# ProProject_Access_Control_Interface_2024.net
KiCad netlist of a schematic drawn in EasyEDA Pro
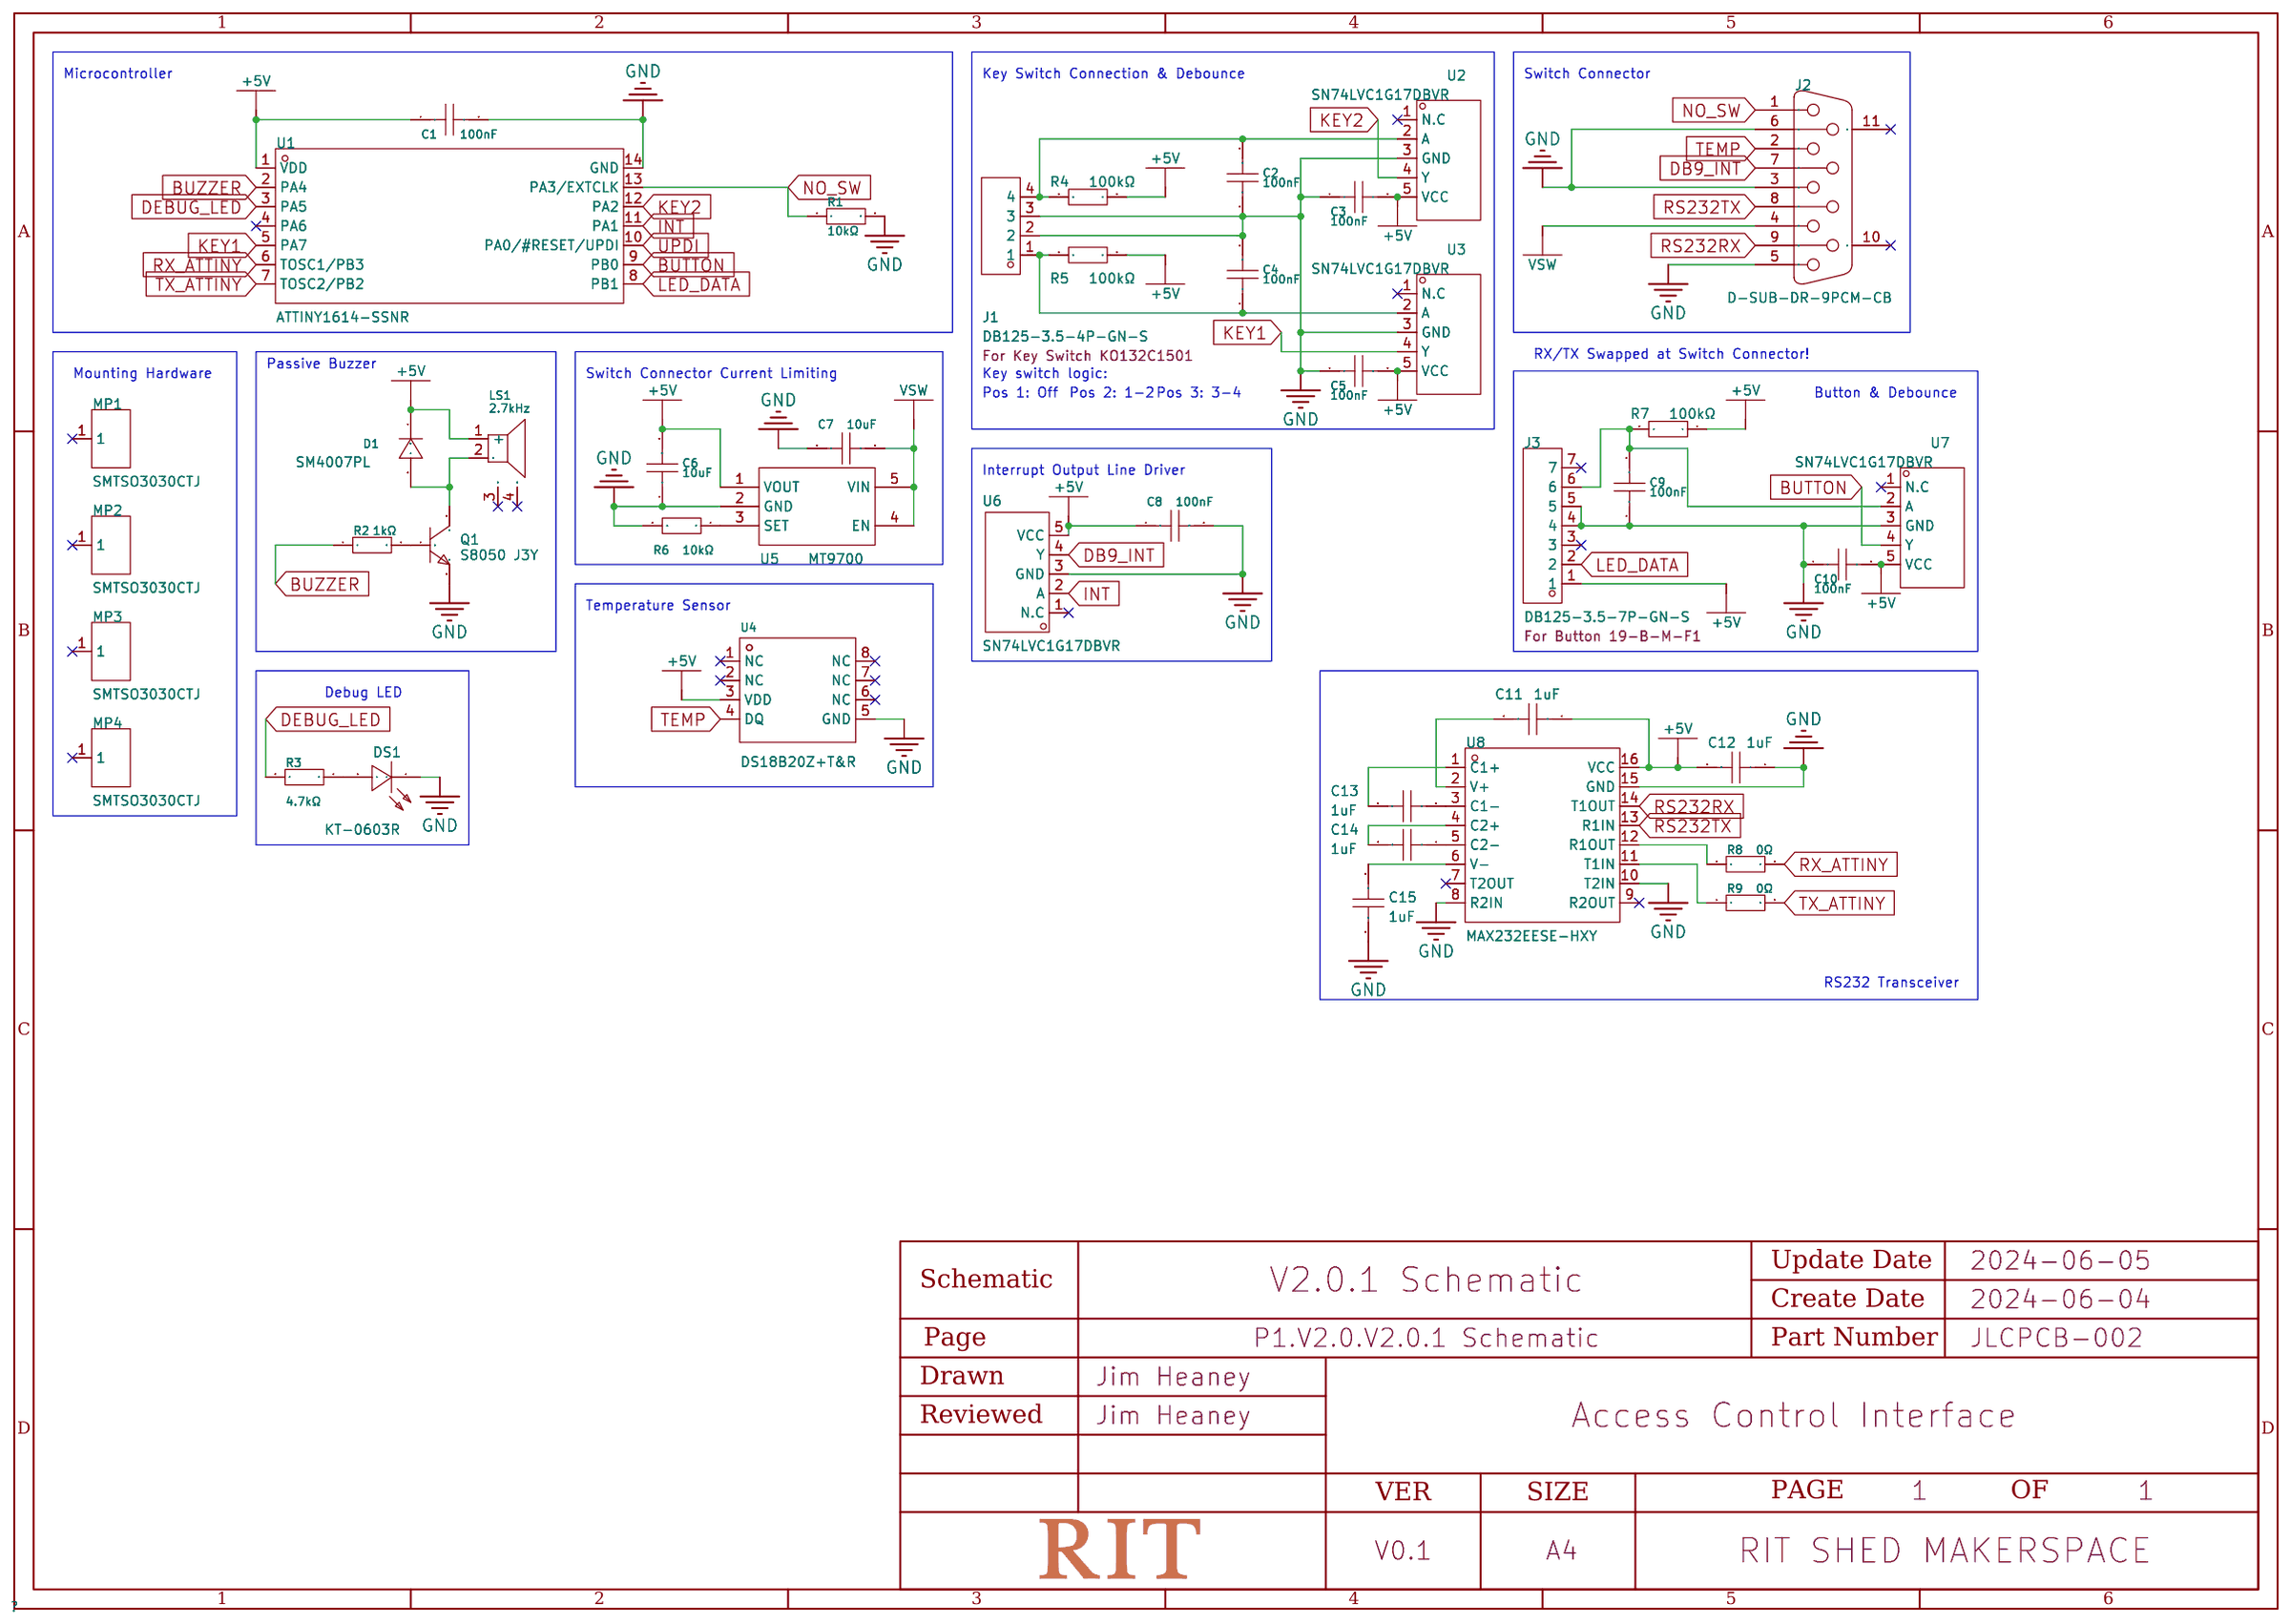
[diagram p0: schematic sheet]

(export (version "E")
  (design (tool "Eeschema 10.0.6"))
  (components
    (comp (ref "C1")
      (value "100nF")
      (footprint "easyedapro:C0603")
      (fields
        (field (name "Manufacturer Part") "CC0603KRX7R9BB104")
        (field (name "Manufacturer") "YAGEO(国巨)")
      )
      (libsource (lib "easyedapro") (part "CC0603KRX7R9BB104"))
    )
    (comp (ref "C2")
      (value "100nF")
      (footprint "easyedapro:C0603")
      (fields
        (field (name "Manufacturer Part") "CC0603KRX7R9BB104")
        (field (name "Manufacturer") "YAGEO(国巨)")
      )
      (libsource (lib "easyedapro") (part "CC0603KRX7R9BB104"))
    )
    (comp (ref "C3")
      (value "100nF")
      (footprint "easyedapro:C0603")
      (fields
        (field (name "Manufacturer Part") "CC0603KRX7R9BB104")
        (field (name "Manufacturer") "YAGEO(国巨)")
      )
      (libsource (lib "easyedapro") (part "CC0603KRX7R9BB104"))
    )
    (comp (ref "C4")
      (value "100nF")
      (footprint "easyedapro:C0603")
      (fields
        (field (name "Manufacturer Part") "CC0603KRX7R9BB104")
        (field (name "Manufacturer") "YAGEO(国巨)")
      )
      (libsource (lib "easyedapro") (part "CC0603KRX7R9BB104"))
    )
    (comp (ref "C5")
      (value "100nF")
      (footprint "easyedapro:C0603")
      (fields
        (field (name "Manufacturer Part") "CC0603KRX7R9BB104")
        (field (name "Manufacturer") "YAGEO(国巨)")
      )
      (libsource (lib "easyedapro") (part "CC0603KRX7R9BB104"))
    )
    (comp (ref "C6")
      (value "10uF")
      (footprint "easyedapro:C0603")
      (fields
        (field (name "Manufacturer Part") "CL10A106MA8NRNC")
        (field (name "Manufacturer") "SAMSUNG(三星)")
      )
      (libsource (lib "easyedapro") (part "CL10A106MA8NRNC"))
    )
    (comp (ref "C7")
      (value "10uF")
      (footprint "easyedapro:C0603")
      (fields
        (field (name "Manufacturer Part") "CL10A106MA8NRNC")
        (field (name "Manufacturer") "SAMSUNG(三星)")
      )
      (libsource (lib "easyedapro") (part "CL10A106MA8NRNC"))
    )
    (comp (ref "C8")
      (value "100nF")
      (footprint "easyedapro:C0603")
      (fields
        (field (name "Manufacturer Part") "CC0603KRX7R9BB104")
        (field (name "Manufacturer") "YAGEO(国巨)")
      )
      (libsource (lib "easyedapro") (part "CC0603KRX7R9BB104"))
    )
    (comp (ref "C9")
      (value "100nF")
      (footprint "easyedapro:C0603")
      (fields
        (field (name "Manufacturer Part") "CC0603KRX7R9BB104")
        (field (name "Manufacturer") "YAGEO(国巨)")
      )
      (libsource (lib "easyedapro") (part "CC0603KRX7R9BB104"))
    )
    (comp (ref "C10")
      (value "100nF")
      (footprint "easyedapro:C0603")
      (fields
        (field (name "Manufacturer Part") "CC0603KRX7R9BB104")
        (field (name "Manufacturer") "YAGEO(国巨)")
      )
      (libsource (lib "easyedapro") (part "CC0603KRX7R9BB104"))
    )
    (comp (ref "C11")
      (value "1uF")
      (footprint "easyedapro:C0603")
      (fields
        (field (name "Manufacturer Part") "CL10A105KB8NNNC")
        (field (name "Manufacturer") "SAMSUNG(三星)")
      )
      (libsource (lib "easyedapro") (part "CL10A105KB8NNNC"))
    )
    (comp (ref "C12")
      (value "1uF")
      (footprint "easyedapro:C0603")
      (fields
        (field (name "Manufacturer Part") "CL10A105KB8NNNC")
        (field (name "Manufacturer") "SAMSUNG(三星)")
      )
      (libsource (lib "easyedapro") (part "CL10A105KB8NNNC"))
    )
    (comp (ref "C13")
      (value "1uF")
      (footprint "easyedapro:C0603")
      (fields
        (field (name "Manufacturer Part") "CL10A105KB8NNNC")
        (field (name "Manufacturer") "SAMSUNG(三星)")
      )
      (libsource (lib "easyedapro") (part "CL10A105KB8NNNC"))
    )
    (comp (ref "C14")
      (value "1uF")
      (footprint "easyedapro:C0603")
      (fields
        (field (name "Manufacturer Part") "CL10A105KB8NNNC")
        (field (name "Manufacturer") "SAMSUNG(三星)")
      )
      (libsource (lib "easyedapro") (part "CL10A105KB8NNNC"))
    )
    (comp (ref "C15")
      (value "1uF")
      (footprint "easyedapro:C0603")
      (fields
        (field (name "Manufacturer Part") "CL10A105KB8NNNC")
        (field (name "Manufacturer") "SAMSUNG(三星)")
      )
      (libsource (lib "easyedapro") (part "CL10A105KB8NNNC"))
    )
    (comp (ref "D1")
      (value "SM4007PL")
      (footprint "easyedapro:SOD-123F_L2.8-W1.8-LS3.7-RD")
      (fields (field (name "Manufacturer") "MDD"))
      (libsource (lib "easyedapro") (part "SM4007PL"))
    )
    (comp (ref "DS1")
      (value "KT-0603R")
      (footprint "easyedapro:LED0603-RD")
      (fields (field (name "Manufacturer") "KENTO"))
      (libsource (lib "easyedapro") (part "KT-0603R"))
    )
    (comp (ref "J1")
      (value "DB125-3.5-4P-GN-S")
      (footprint "easyedapro:CONN-TH_DB125-3.5-4P-GN")
      (description "For Key Switch KO132C1501")
      (fields (field (name "Manufacturer") "DORABO(地博电气)"))
      (libsource (lib "easyedapro") (part "DB125-3.5-4P-GN"))
    )
    (comp (ref "J2")
      (value "D-SUB-DR-9PCM-CB")
      (footprint "easyedapro:DB9-TH_ID09S33E4GV00LF")
      (fields (field (name "Manufacturer") "XUNPU(讯普)"))
      (libsource (lib "easyedapro") (part "D-SUB-DR-9PCM-CB"))
    )
    (comp (ref "J3")
      (value "DB125-3.5-7P-GN-S")
      (footprint "easyedapro:CONN-TH_7P-P3.50_DORABO_DB125-3.5-7P-GN-S")
      (description "For Button 19-B-M-F1")
      (fields (field (name "Manufacturer") "DORABO(地博电气)"))
      (libsource (lib "easyedapro") (part "DB125-3.5-7P-GN-S"))
    )
    (comp (ref "LS1")
      (value "2.7kHz")
      (footprint "easyedapro:BUZ-SMD_4P-L8.5-W8.5-P8.50-TL")
      (fields (field (name "Manufacturer Part") "MLT-8540") (field (name "Manufacturer") "华能"))
      (libsource (lib "easyedapro") (part "MLT-8540"))
    )
    (comp (ref "MP1")
      (value "SMTSO3030CTJ")
      (footprint "easyedapro:SMD_BD5.6-D4.1")
      (description "specifications:M3X3 surface treatment:镀锡 Product Description:- material quality:-")
      (fields (field (name "Manufacturer") "Sinhoo(雄和远景)"))
      (libsource (lib "easyedapro") (part "SMTSO3030CTJ"))
    )
    (comp (ref "MP2")
      (value "SMTSO3030CTJ")
      (footprint "easyedapro:SMD_BD5.6-D4.1")
      (description "specifications:M3X3 surface treatment:镀锡 Product Description:- material quality:-")
      (fields (field (name "Manufacturer") "Sinhoo(雄和远景)"))
      (libsource (lib "easyedapro") (part "SMTSO3030CTJ"))
    )
    (comp (ref "MP3")
      (value "SMTSO3030CTJ")
      (footprint "easyedapro:SMD_BD5.6-D4.1")
      (description "specifications:M3X3 surface treatment:镀锡 Product Description:- material quality:-")
      (fields (field (name "Manufacturer") "Sinhoo(雄和远景)"))
      (libsource (lib "easyedapro") (part "SMTSO3030CTJ"))
    )
    (comp (ref "MP4")
      (value "SMTSO3030CTJ")
      (footprint "easyedapro:SMD_BD5.6-D4.1")
      (description "specifications:M3X3 surface treatment:镀锡 Product Description:- material quality:-")
      (fields (field (name "Manufacturer") "Sinhoo(雄和远景)"))
      (libsource (lib "easyedapro") (part "SMTSO3030CTJ"))
    )
    (comp (ref "Q1")
      (value "S8050 J3Y")
      (footprint "easyedapro:SOT-23-3_L3.0-W1.7-P0.95-LS2.9-BR")
      (fields (field (name "Manufacturer") "CJ(江苏长电/长晶)"))
      (libsource (lib "easyedapro") (part "S8050_C2146"))
    )
    (comp (ref "R1")
      (value "10kΩ")
      (footprint "easyedapro:R0603")
      (fields
        (field (name "Manufacturer Part") "0603WAF1002T5E")
        (field (name "Manufacturer") "UNI-ROYAL(厚声)")
      )
      (libsource (lib "easyedapro") (part "0603WAF1002T5E"))
    )
    (comp (ref "R2")
      (value "1kΩ")
      (footprint "easyedapro:R0603")
      (fields
        (field (name "Manufacturer Part") "0603WAF1001T5E")
        (field (name "Manufacturer") "UNI-ROYAL(厚声)")
      )
      (libsource (lib "easyedapro") (part "0603WAF1001T5E"))
    )
    (comp (ref "R3")
      (value "4.7kΩ")
      (footprint "easyedapro:R0603")
      (fields
        (field (name "Manufacturer Part") "0603WAF4701T5E")
        (field (name "Manufacturer") "UNI-ROYAL(厚声)")
      )
      (libsource (lib "easyedapro") (part "0603WAF4701T5E"))
    )
    (comp (ref "R4")
      (value "100kΩ")
      (footprint "easyedapro:R0603")
      (fields
        (field (name "Manufacturer Part") "0603WAF1003T5E")
        (field (name "Manufacturer") "UNI-ROYAL(厚声)")
      )
      (libsource (lib "easyedapro") (part "0603WAF1003T5E"))
    )
    (comp (ref "R5")
      (value "100kΩ")
      (footprint "easyedapro:R0603")
      (fields
        (field (name "Manufacturer Part") "0603WAF1003T5E")
        (field (name "Manufacturer") "UNI-ROYAL(厚声)")
      )
      (libsource (lib "easyedapro") (part "0603WAF1003T5E"))
    )
    (comp (ref "R6")
      (value "10kΩ")
      (footprint "easyedapro:R0603")
      (fields
        (field (name "Manufacturer Part") "0603WAF1002T5E")
        (field (name "Manufacturer") "UNI-ROYAL(厚声)")
      )
      (libsource (lib "easyedapro") (part "0603WAF1002T5E"))
    )
    (comp (ref "R7")
      (value "100kΩ")
      (footprint "easyedapro:R0603")
      (fields
        (field (name "Manufacturer Part") "0603WAF1003T5E")
        (field (name "Manufacturer") "UNI-ROYAL(厚声)")
      )
      (libsource (lib "easyedapro") (part "0603WAF1003T5E"))
    )
    (comp (ref "R8")
      (value "0Ω")
      (footprint "easyedapro:R1206")
      (fields
        (field (name "Manufacturer Part") "1206W4F0000T5E")
        (field (name "Manufacturer") "UNI-ROYAL(厚声)")
      )
      (libsource (lib "easyedapro") (part "1206W4F0000T5E"))
    )
    (comp (ref "R9")
      (value "0Ω")
      (footprint "easyedapro:R1206")
      (fields
        (field (name "Manufacturer Part") "1206W4F0000T5E")
        (field (name "Manufacturer") "UNI-ROYAL(厚声)")
      )
      (libsource (lib "easyedapro") (part "1206W4F0000T5E"))
    )
    (comp (ref "U1")
      (value "ATTINY1614-SSNR")
      (footprint "easyedapro:SOIC-14_L8.7-W3.9-P1.27-LS6.0-BL")
      (fields (field (name "Manufacturer") "MICROCHIP(美国微芯)"))
      (libsource (lib "easyedapro") (part "ATTINY1614-SSNR"))
    )
    (comp (ref "U2")
      (value "SN74LVC1G17DBVR")
      (footprint "easyedapro:SOT-23-5_L3.0-W1.7-P0.95-LS2.8-BR")
      (fields (field (name "Manufacturer") "TI(德州仪器)"))
      (libsource (lib "easyedapro") (part "SN74LVC1G17DBVR"))
    )
    (comp (ref "U3")
      (value "SN74LVC1G17DBVR")
      (footprint "easyedapro:SOT-23-5_L3.0-W1.7-P0.95-LS2.8-BR")
      (fields (field (name "Manufacturer") "TI(德州仪器)"))
      (libsource (lib "easyedapro") (part "SN74LVC1G17DBVR"))
    )
    (comp (ref "U4")
      (value "DS18B20Z+T&R")
      (footprint "easyedapro:SOIC-8_L4.9-W3.9-P1.27-LS6.0-BL")
      (description "Supply Voltage:3V~5.5V Supply Voltage:3V~5.5V")
      (fields (field (name "Manufacturer") "ADI(亚德诺)/MAXIM(美信)"))
      (libsource (lib "easyedapro") (part "DS18B20Z+T&amp;R"))
    )
    (comp (ref "U5")
      (value "MT9700")
      (footprint "easyedapro:SOT-23-5_L3.0-W1.7-P0.95-LS2.8-BR")
      (fields (field (name "Manufacturer") "西安航天民芯"))
      (libsource (lib "easyedapro") (part "MT9700"))
    )
    (comp (ref "U6")
      (value "SN74LVC1G17DBVR")
      (footprint "easyedapro:SOT-23-5_L3.0-W1.7-P0.95-LS2.8-BR")
      (fields (field (name "Manufacturer") "TI(德州仪器)"))
      (libsource (lib "easyedapro") (part "SN74LVC1G17DBVR"))
    )
    (comp (ref "U7")
      (value "SN74LVC1G17DBVR")
      (footprint "easyedapro:SOT-23-5_L3.0-W1.7-P0.95-LS2.8-BR")
      (fields (field (name "Manufacturer") "TI(德州仪器)"))
      (libsource (lib "easyedapro") (part "SN74LVC1G17DBVR"))
    )
    (comp (ref "U8")
      (value "MAX232EESE-HXY")
      (footprint "easyedapro:SOP-16_L9.9-W3.9-P1.27-LS6.0-BL")
      (description "Driver/receiver:2/2 Data Rate:120Kbps Data Rate:120Kbps Supply Voltage:5V Supply Voltage:5V")
      (fields (field (name "Manufacturer") "HXY MOSFET(华轩阳电子)"))
      (libsource (lib "easyedapro") (part "MAX232EESE-HXY"))
    )
  )
  (nets
    (net (code "1") (name "+5V") (class "Default")
      (node (ref "C1") (pin "1") (pinfunction "1_1") (pintype "input"))
      (node (ref "C10") (pin "2") (pinfunction "2_2") (pintype "input"))
      (node (ref "C11") (pin "1") (pinfunction "1_1") (pintype "unspecified"))
      (node (ref "C12") (pin "2") (pinfunction "2_2") (pintype "unspecified"))
      (node (ref "C3") (pin "2") (pinfunction "2_2") (pintype "input"))
      (node (ref "C5") (pin "2") (pinfunction "2_2") (pintype "input"))
      (node (ref "C6") (pin "2") (pinfunction "2_2") (pintype "input"))
      (node (ref "C8") (pin "1") (pinfunction "1_1") (pintype "input"))
      (node (ref "D1") (pin "1") (pinfunction "C_1") (pintype "input"))
      (node (ref "J3") (pin "1") (pinfunction "1_1") (pintype "unspecified"))
      (node (ref "LS1") (pin "1") (pinfunction "+_1") (pintype "input"))
      (node (ref "R4") (pin "1") (pinfunction "1_1") (pintype "input"))
      (node (ref "R5") (pin "1") (pinfunction "1_1") (pintype "input"))
      (node (ref "R7") (pin "1") (pinfunction "1_1") (pintype "input"))
      (node (ref "U1") (pin "1") (pinfunction "VDD_1") (pintype "input"))
      (node (ref "U2") (pin "5") (pinfunction "VCC_5") (pintype "input"))
      (node (ref "U3") (pin "5") (pinfunction "VCC_5") (pintype "input"))
      (node (ref "U4") (pin "3") (pinfunction "VDD_3") (pintype "input"))
      (node (ref "U5") (pin "1") (pinfunction "VOUT_1") (pintype "unspecified"))
      (node (ref "U6") (pin "5") (pinfunction "VCC_5") (pintype "input"))
      (node (ref "U7") (pin "5") (pinfunction "VCC_5") (pintype "input"))
      (node (ref "U8") (pin "16") (pinfunction "VCC_16") (pintype "unspecified"))
    )
    (net (code "2") (name "BUTTON") (class "Default")
      (node (ref "U1") (pin "9") (pinfunction "PB0_9") (pintype "input"))
      (node (ref "U7") (pin "4") (pinfunction "Y_4") (pintype "input"))
    )
    (net (code "3") (name "BUZZER") (class "Default")
      (node (ref "R2") (pin "1") (pinfunction "1_1") (pintype "input"))
      (node (ref "U1") (pin "2") (pinfunction "PA4_2") (pintype "input"))
    )
    (net (code "4") (name "DB9_INT") (class "Default")
      (node (ref "J2") (pin "7") (pinfunction "7_7") (pintype "input"))
      (node (ref "U6") (pin "4") (pinfunction "Y_4") (pintype "input"))
    )
    (net (code "5") (name "DEBUG_LED") (class "Default")
      (node (ref "R3") (pin "2") (pinfunction "2_2") (pintype "input"))
      (node (ref "U1") (pin "3") (pinfunction "PA5_3") (pintype "input"))
    )
    (net (code "6") (name "GND") (class "Default")
      (node (ref "C1") (pin "2") (pinfunction "2_2") (pintype "input"))
      (node (ref "C10") (pin "1") (pinfunction "1_1") (pintype "input"))
      (node (ref "C12") (pin "1") (pinfunction "1_1") (pintype "unspecified"))
      (node (ref "C15") (pin "1") (pinfunction "1_1") (pintype "unspecified"))
      (node (ref "C2") (pin "1") (pinfunction "1_1") (pintype "input"))
      (node (ref "C3") (pin "1") (pinfunction "1_1") (pintype "input"))
      (node (ref "C4") (pin "2") (pinfunction "2_2") (pintype "input"))
      (node (ref "C5") (pin "1") (pinfunction "1_1") (pintype "input"))
      (node (ref "C6") (pin "1") (pinfunction "1_1") (pintype "input"))
      (node (ref "C7") (pin "2") (pinfunction "2_2") (pintype "input"))
      (node (ref "C8") (pin "2") (pinfunction "2_2") (pintype "input"))
      (node (ref "C9") (pin "1") (pinfunction "1_1") (pintype "input"))
      (node (ref "DS1") (pin "1") (pinfunction "K_1") (pintype "input"))
      (node (ref "J1") (pin "2") (pinfunction "2_2") (pintype "unspecified"))
      (node (ref "J1") (pin "3") (pinfunction "3_3") (pintype "unspecified"))
      (node (ref "J2") (pin "3") (pinfunction "3_3") (pintype "input"))
      (node (ref "J2") (pin "5") (pinfunction "5_5") (pintype "input"))
      (node (ref "J2") (pin "6") (pinfunction "6_6") (pintype "input"))
      (node (ref "J3") (pin "4") (pinfunction "4_4") (pintype "unspecified"))
      (node (ref "J3") (pin "5") (pinfunction "5_5") (pintype "unspecified"))
      (node (ref "Q1") (pin "2") (pinfunction "E_2") (pintype "unspecified"))
      (node (ref "R1") (pin "2") (pinfunction "2_2") (pintype "input"))
      (node (ref "R6") (pin "2") (pinfunction "2_2") (pintype "input"))
      (node (ref "U1") (pin "14") (pinfunction "GND_14") (pintype "input"))
      (node (ref "U2") (pin "3") (pinfunction "GND_3") (pintype "input"))
      (node (ref "U3") (pin "3") (pinfunction "GND_3") (pintype "input"))
      (node (ref "U4") (pin "5") (pinfunction "GND_5") (pintype "input"))
      (node (ref "U5") (pin "2") (pinfunction "GND_2") (pintype "unspecified"))
      (node (ref "U6") (pin "3") (pinfunction "GND_3") (pintype "input"))
      (node (ref "U7") (pin "3") (pinfunction "GND_3") (pintype "input"))
      (node (ref "U8") (pin "10") (pinfunction "T2IN_10") (pintype "unspecified"))
      (node (ref "U8") (pin "15") (pinfunction "GND_15") (pintype "unspecified"))
      (node (ref "U8") (pin "8") (pinfunction "R2IN_8") (pintype "unspecified"))
    )
    (net (code "7") (name "INT") (class "Default")
      (node (ref "U1") (pin "11") (pinfunction "PA1_11") (pintype "input"))
      (node (ref "U6") (pin "2") (pinfunction "A_2") (pintype "input"))
    )
    (net (code "8") (name "KEY1") (class "Default")
      (node (ref "U1") (pin "5") (pinfunction "PA7_5") (pintype "input"))
      (node (ref "U3") (pin "4") (pinfunction "Y_4") (pintype "input"))
    )
    (net (code "9") (name "KEY2") (class "Default")
      (node (ref "U1") (pin "12") (pinfunction "PA2_12") (pintype "input"))
      (node (ref "U2") (pin "4") (pinfunction "Y_4") (pintype "input"))
    )
    (net (code "10") (name "LED_DATA") (class "Default")
      (node (ref "J3") (pin "2") (pinfunction "2_2") (pintype "unspecified"))
      (node (ref "U1") (pin "8") (pinfunction "PB1_8") (pintype "input"))
    )
    (net (code "11") (name "NO_SW") (class "Default")
      (node (ref "J2") (pin "1") (pinfunction "1_1") (pintype "input"))
      (node (ref "R1") (pin "1") (pinfunction "1_1") (pintype "input"))
      (node (ref "U1") (pin "13") (pinfunction "PA3/EXTCLK_13") (pintype "input"))
    )
    (net (code "12") (name "Net-(D1-A)") (class "Default")
      (node (ref "D1") (pin "2") (pinfunction "A_2") (pintype "input"))
      (node (ref "LS1") (pin "2") (pinfunction "2_2") (pintype "input"))
      (node (ref "Q1") (pin "3") (pinfunction "C_3") (pintype "unspecified"))
    )
    (net (code "13") (name "Net-(DS1-A)") (class "Default")
      (node (ref "DS1") (pin "2") (pinfunction "A_2") (pintype "input"))
      (node (ref "R3") (pin "1") (pinfunction "1_1") (pintype "input"))
    )
    (net (code "14") (name "Net-(Q1-B)") (class "Default")
      (node (ref "Q1") (pin "1") (pinfunction "B_1") (pintype "unspecified"))
      (node (ref "R2") (pin "2") (pinfunction "2_2") (pintype "input"))
    )
    (net (code "15") (name "Net-(U2-A)") (class "Default")
      (node (ref "C2") (pin "2") (pinfunction "2_2") (pintype "input"))
      (node (ref "J1") (pin "4") (pinfunction "4_4") (pintype "unspecified"))
      (node (ref "R4") (pin "2") (pinfunction "2_2") (pintype "input"))
      (node (ref "U2") (pin "2") (pinfunction "A_2") (pintype "input"))
    )
    (net (code "16") (name "Net-(U3-A)") (class "Default")
      (node (ref "C4") (pin "1") (pinfunction "1_1") (pintype "input"))
      (node (ref "J1") (pin "1") (pinfunction "1_1") (pintype "unspecified"))
      (node (ref "R5") (pin "2") (pinfunction "2_2") (pintype "input"))
      (node (ref "U3") (pin "2") (pinfunction "A_2") (pintype "input"))
    )
    (net (code "17") (name "Net-(U5-SET)") (class "Default")
      (node (ref "R6") (pin "1") (pinfunction "1_1") (pintype "input"))
      (node (ref "U5") (pin "3") (pinfunction "SET_3") (pintype "unspecified"))
    )
    (net (code "18") (name "Net-(U7-A)") (class "Default")
      (node (ref "C9") (pin "2") (pinfunction "2_2") (pintype "input"))
      (node (ref "J3") (pin "6") (pinfunction "6_6") (pintype "unspecified"))
      (node (ref "R7") (pin "2") (pinfunction "2_2") (pintype "input"))
      (node (ref "U7") (pin "2") (pinfunction "A_2") (pintype "input"))
    )
    (net (code "19") (name "Net-(U8-C1+)") (class "Default")
      (node (ref "C13") (pin "2") (pinfunction "2_2") (pintype "unspecified"))
      (node (ref "U8") (pin "1") (pinfunction "C1+_1") (pintype "unspecified"))
    )
    (net (code "20") (name "Net-(U8-C1-)") (class "Default")
      (node (ref "C13") (pin "1") (pinfunction "1_1") (pintype "unspecified"))
      (node (ref "U8") (pin "3") (pinfunction "C1-_3") (pintype "unspecified"))
    )
    (net (code "21") (name "Net-(U8-C2+)") (class "Default")
      (node (ref "C14") (pin "2") (pinfunction "2_2") (pintype "unspecified"))
      (node (ref "U8") (pin "4") (pinfunction "C2+_4") (pintype "unspecified"))
    )
    (net (code "22") (name "Net-(U8-C2-)") (class "Default")
      (node (ref "C14") (pin "1") (pinfunction "1_1") (pintype "unspecified"))
      (node (ref "U8") (pin "5") (pinfunction "C2-_5") (pintype "unspecified"))
    )
    (net (code "23") (name "Net-(U8-R1OUT)") (class "Default")
      (node (ref "R8") (pin "1") (pinfunction "1_1") (pintype "input"))
      (node (ref "U8") (pin "12") (pinfunction "R1OUT_12") (pintype "unspecified"))
    )
    (net (code "24") (name "Net-(U8-T1IN)") (class "Default")
      (node (ref "R9") (pin "1") (pinfunction "1_1") (pintype "input"))
      (node (ref "U8") (pin "11") (pinfunction "T1IN_11") (pintype "unspecified"))
    )
    (net (code "25") (name "Net-(U8-V+)") (class "Default")
      (node (ref "C11") (pin "2") (pinfunction "2_2") (pintype "unspecified"))
      (node (ref "U8") (pin "2") (pinfunction "V+_2") (pintype "unspecified"))
    )
    (net (code "26") (name "Net-(U8-V-)") (class "Default")
      (node (ref "C15") (pin "2") (pinfunction "2_2") (pintype "unspecified"))
      (node (ref "U8") (pin "6") (pinfunction "V-_6") (pintype "unspecified"))
    )
    (net (code "27") (name "RS232RX") (class "Default")
      (node (ref "J2") (pin "9") (pinfunction "9_9") (pintype "input"))
      (node (ref "U8") (pin "14") (pinfunction "T1OUT_14") (pintype "unspecified"))
    )
    (net (code "28") (name "RS232TX") (class "Default")
      (node (ref "J2") (pin "8") (pinfunction "8_8") (pintype "input"))
      (node (ref "U8") (pin "13") (pinfunction "R1IN_13") (pintype "unspecified"))
    )
    (net (code "29") (name "RX_ATTINY") (class "Default")
      (node (ref "R8") (pin "2") (pinfunction "2_2") (pintype "input"))
      (node (ref "U1") (pin "6") (pinfunction "TOSC1/PB3_6") (pintype "input"))
    )
    (net (code "30") (name "TEMP") (class "Default")
      (node (ref "J2") (pin "2") (pinfunction "2_2") (pintype "input"))
      (node (ref "U4") (pin "4") (pinfunction "DQ_4") (pintype "input"))
    )
    (net (code "31") (name "TX_ATTINY") (class "Default")
      (node (ref "R9") (pin "2") (pinfunction "2_2") (pintype "input"))
      (node (ref "U1") (pin "7") (pinfunction "TOSC2/PB2_7") (pintype "input"))
    )
    (net (code "32") (name "UPDI") (class "Default")
      (node (ref "U1") (pin "10") (pinfunction "PA0/#RESET/UPDI_10") (pintype "input"))
    )
    (net (code "33") (name "VSW") (class "Default")
      (node (ref "C7") (pin "1") (pinfunction "1_1") (pintype "input"))
      (node (ref "J2") (pin "4") (pinfunction "4_4") (pintype "input"))
      (node (ref "U5") (pin "4") (pinfunction "EN_4") (pintype "unspecified"))
      (node (ref "U5") (pin "5") (pinfunction "VIN_5") (pintype "unspecified"))
    )
    (net (code "34") (name "unconnected-(J2-MH1-Pad10)") (class "Default")
      (node (ref "J2") (pin "10") (pinfunction "MH1_10") (pintype "input+no_connect"))
    )
    (net (code "35") (name "unconnected-(J2-MH2-Pad11)") (class "Default")
      (node (ref "J2") (pin "11") (pinfunction "MH2_11") (pintype "input+no_connect"))
    )
    (net (code "36") (name "unconnected-(J3-Pad3)") (class "Default")
      (node (ref "J3") (pin "3") (pinfunction "3_3") (pintype "unspecified+no_connect"))
    )
    (net (code "37") (name "unconnected-(J3-Pad7)") (class "Default")
      (node (ref "J3") (pin "7") (pinfunction "7_7") (pintype "unspecified+no_connect"))
    )
    (net (code "38") (name "unconnected-(LS1-NC-Pad3)") (class "Default")
      (node (ref "LS1") (pin "3") (pinfunction "NC_3") (pintype "input+no_connect"))
    )
    (net (code "39") (name "unconnected-(LS1-NC-Pad4)") (class "Default")
      (node (ref "LS1") (pin "4") (pinfunction "NC_4") (pintype "input+no_connect"))
    )
    (net (code "40") (name "unconnected-(MP1-Pad1)") (class "Default")
      (node (ref "MP1") (pin "1") (pinfunction "1_1") (pintype "unspecified+no_connect"))
    )
    (net (code "41") (name "unconnected-(MP2-Pad1)") (class "Default")
      (node (ref "MP2") (pin "1") (pinfunction "1_1") (pintype "unspecified+no_connect"))
    )
    (net (code "42") (name "unconnected-(MP3-Pad1)") (class "Default")
      (node (ref "MP3") (pin "1") (pinfunction "1_1") (pintype "unspecified+no_connect"))
    )
    (net (code "43") (name "unconnected-(MP4-Pad1)") (class "Default")
      (node (ref "MP4") (pin "1") (pinfunction "1_1") (pintype "unspecified+no_connect"))
    )
    (net (code "44") (name "unconnected-(U1-PA6-Pad4)") (class "Default")
      (node (ref "U1") (pin "4") (pinfunction "PA6_4") (pintype "input+no_connect"))
    )
    (net (code "45") (name "unconnected-(U2-N.C-Pad1)") (class "Default")
      (node (ref "U2") (pin "1") (pinfunction "N.C_1") (pintype "input+no_connect"))
    )
    (net (code "46") (name "unconnected-(U3-N.C-Pad1)") (class "Default")
      (node (ref "U3") (pin "1") (pinfunction "N.C_1") (pintype "input+no_connect"))
    )
    (net (code "47") (name "unconnected-(U4-NC-Pad1)") (class "Default")
      (node (ref "U4") (pin "1") (pinfunction "NC_1") (pintype "input+no_connect"))
    )
    (net (code "48") (name "unconnected-(U4-NC-Pad2)") (class "Default")
      (node (ref "U4") (pin "2") (pinfunction "NC_2") (pintype "input+no_connect"))
    )
    (net (code "49") (name "unconnected-(U4-NC-Pad6)") (class "Default")
      (node (ref "U4") (pin "6") (pinfunction "NC_6") (pintype "input+no_connect"))
    )
    (net (code "50") (name "unconnected-(U4-NC-Pad7)") (class "Default")
      (node (ref "U4") (pin "7") (pinfunction "NC_7") (pintype "input+no_connect"))
    )
    (net (code "51") (name "unconnected-(U4-NC-Pad8)") (class "Default")
      (node (ref "U4") (pin "8") (pinfunction "NC_8") (pintype "input+no_connect"))
    )
    (net (code "52") (name "unconnected-(U6-N.C-Pad1)") (class "Default")
      (node (ref "U6") (pin "1") (pinfunction "N.C_1") (pintype "input+no_connect"))
    )
    (net (code "53") (name "unconnected-(U7-N.C-Pad1)") (class "Default")
      (node (ref "U7") (pin "1") (pinfunction "N.C_1") (pintype "input+no_connect"))
    )
    (net (code "54") (name "unconnected-(U8-R2OUT-Pad9)") (class "Default")
      (node (ref "U8") (pin "9") (pinfunction "R2OUT_9") (pintype "unspecified+no_connect"))
    )
    (net (code "55") (name "unconnected-(U8-T2OUT-Pad7)") (class "Default")
      (node (ref "U8") (pin "7") (pinfunction "T2OUT_7") (pintype "unspecified+no_connect"))
    )
  )
)
